# 9_ZynTra-USB2_0.net
KiCad netlist of a schematic drawn in Altium Designer
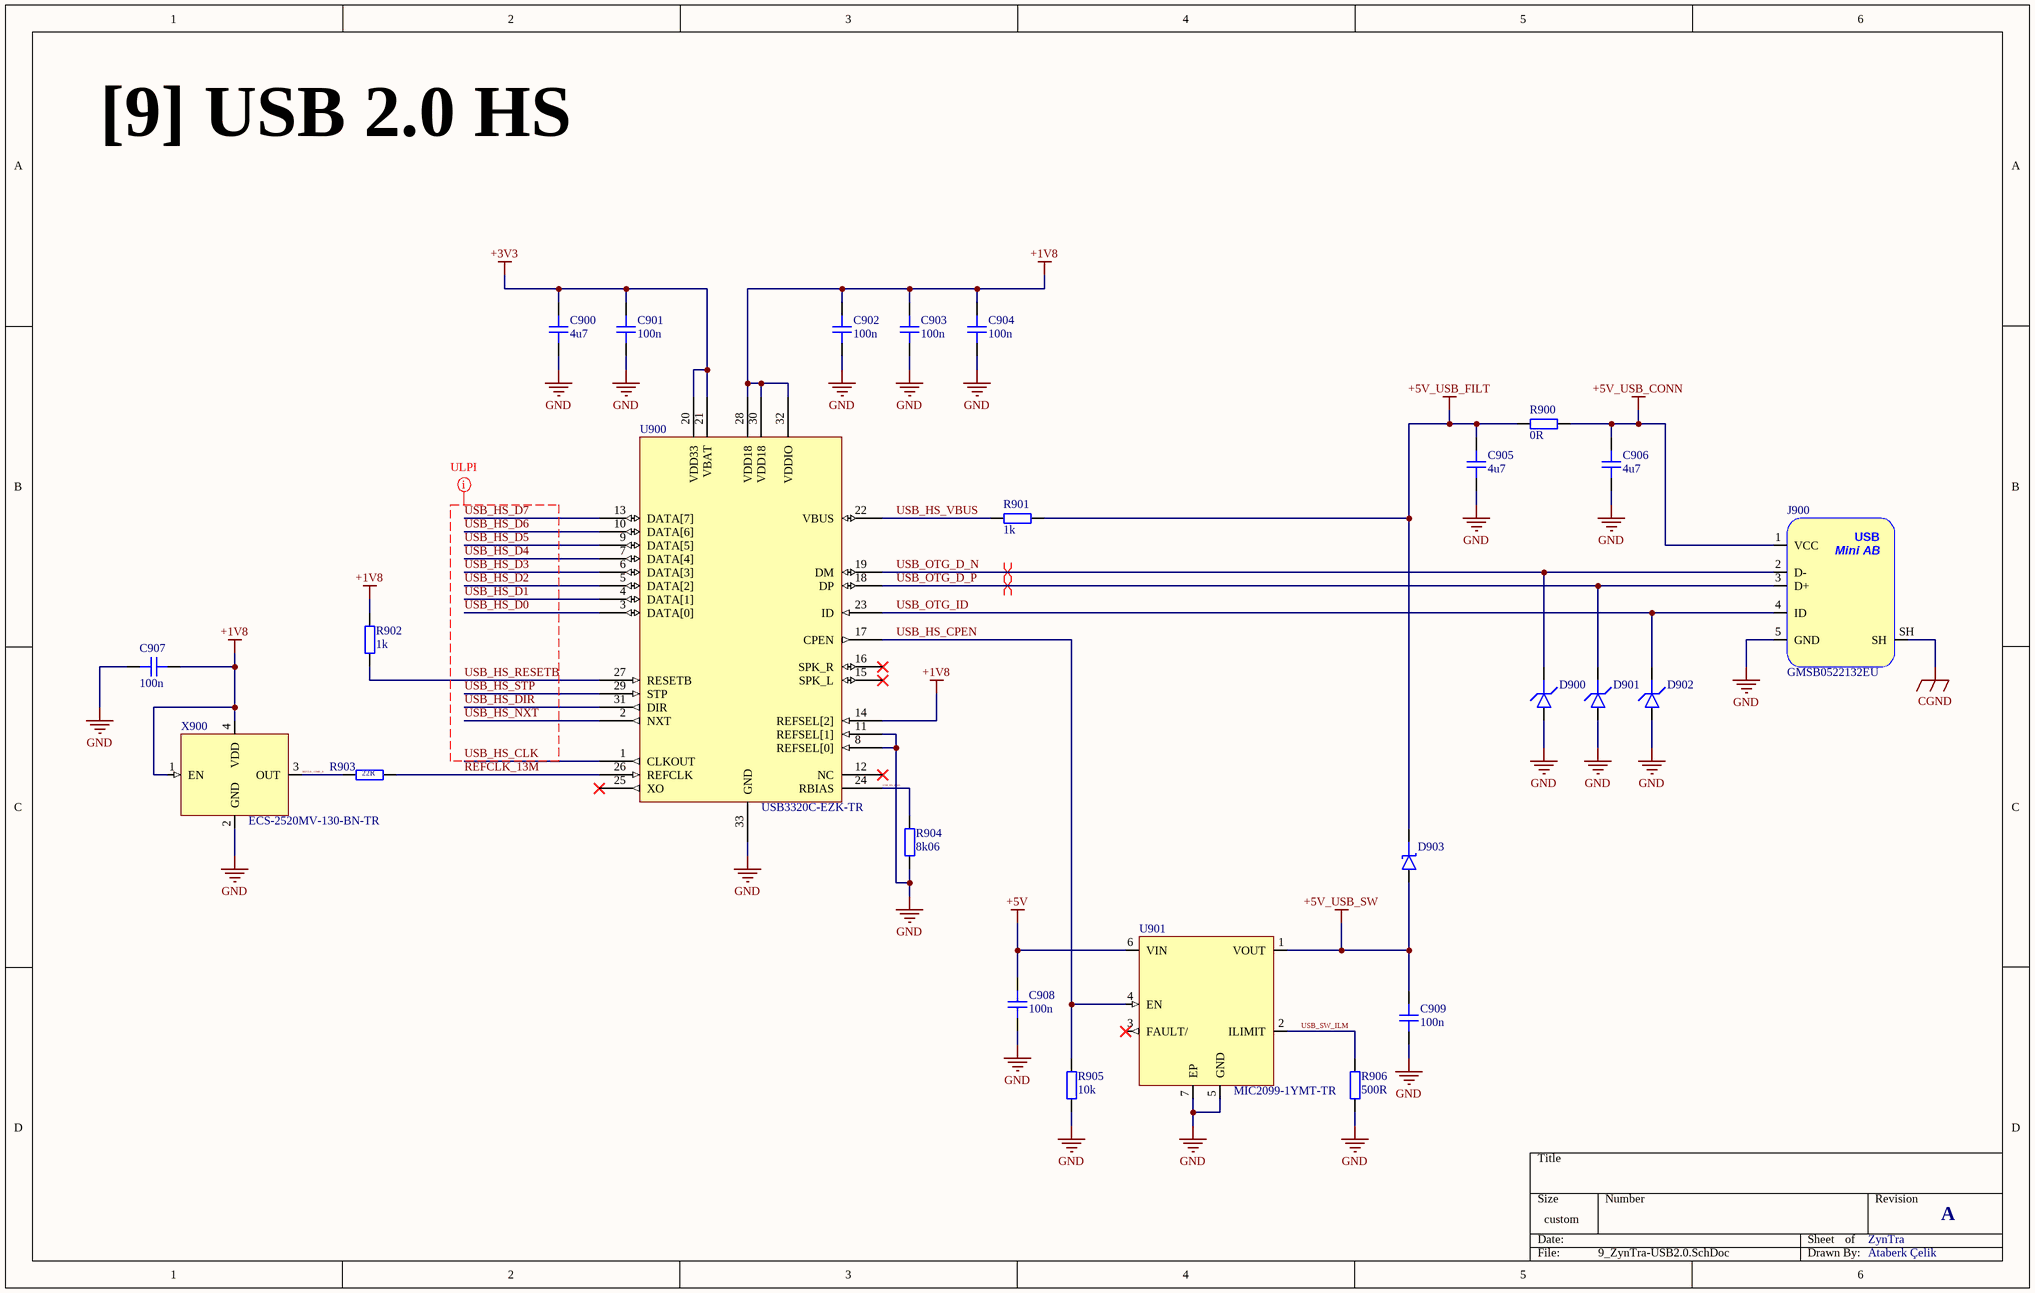
[diagram p0: 9_ZynTra-USB2.0.SchDoc]

(export (version "E")
  (design (tool "Eeschema 10.0.6"))
  (components
    (comp (ref "C900")
      (value "4u7")
      (footprint "CAP_0402")
      (description "Capacitor SMD 0402")
      (libsource (lib "Schematic-Lib-PhilsLab") (part "CAP_0402"))
    )
    (comp (ref "C901")
      (value "100n")
      (footprint "CAP_0201")
      (description "Capacitor SMD 0201")
      (libsource (lib "Schematic-Lib-PhilsLab") (part "CAP_0201"))
    )
    (comp (ref "C902")
      (value "100n")
      (footprint "CAP_0201")
      (description "Capacitor SMD 0201")
      (libsource (lib "Schematic-Lib-PhilsLab") (part "CAP_0201"))
    )
    (comp (ref "C903")
      (value "100n")
      (footprint "CAP_0201")
      (description "Capacitor SMD 0201")
      (libsource (lib "Schematic-Lib-PhilsLab") (part "CAP_0201"))
    )
    (comp (ref "C904")
      (value "100n")
      (footprint "CAP_0201")
      (description "Capacitor SMD 0201")
      (libsource (lib "Schematic-Lib-PhilsLab") (part "CAP_0201"))
    )
    (comp (ref "C905")
      (value "4u7")
      (footprint "CAP_0402")
      (description "Capacitor SMD 0402")
      (libsource (lib "Schematic-Lib-PhilsLab") (part "CAP_0402"))
    )
    (comp (ref "C906")
      (value "4u7")
      (footprint "CAP_0402")
      (description "Capacitor SMD 0402")
      (libsource (lib "Schematic-Lib-PhilsLab") (part "CAP_0402"))
    )
    (comp (ref "C907")
      (value "100n")
      (footprint "CAP_0201")
      (description "Capacitor SMD 0201")
      (libsource (lib "Schematic-Lib-PhilsLab") (part "CAP_0201"))
    )
    (comp (ref "C908")
      (value "100n")
      (footprint "CAP_0201")
      (description "Capacitor SMD 0201")
      (libsource (lib "Schematic-Lib-PhilsLab") (part "CAP_0201"))
    )
    (comp (ref "C909")
      (value "100n")
      (footprint "CAP_0201")
      (description "Capacitor SMD 0201")
      (libsource (lib "Schematic-Lib-PhilsLab") (part "CAP_0201"))
    )
    (comp (ref "D900")
      (value "D_TVS_0402")
      (footprint "D_0402")
      (description "Diode TVS / ESD 0402")
      (libsource (lib "Schematic-Lib-PhilsLab") (part "D_TVS_0402"))
    )
    (comp (ref "D901")
      (value "D_TVS_0402")
      (footprint "D_0402")
      (description "Diode TVS / ESD 0402")
      (libsource (lib "Schematic-Lib-PhilsLab") (part "D_TVS_0402"))
    )
    (comp (ref "D902")
      (value "D_TVS_0402")
      (footprint "D_0402")
      (description "Diode TVS / ESD 0402")
      (libsource (lib "Schematic-Lib-PhilsLab") (part "D_TVS_0402"))
    )
    (comp (ref "D903")
      (value "D_SCHOTTKY_SOD_323")
      (footprint "SOD-323")
      (description "Diode Schottky SMD SOD-323")
      (libsource (lib "Schematic-Lib-PhilsLab") (part "D_SCHOTTKY_SOD_323"))
    )
    (comp (ref "J900")
      (value "GMSB0522132EU")
      (footprint "GMSB0522132EU")
      (description "USB 2.0 Mini AB Receptacle Right Angle Through-Hole")
      (fields (field (name "MANUFACTURER") "Amphenol"))
      (libsource (lib "Schematic-Lib-PhilsLab") (part "GMSB0522132EU"))
    )
    (comp (ref "R900")
      (value "0R")
      (footprint "RES_0402")
      (description "Resistor SMD 0402")
      (libsource (lib "Schematic-Lib-PhilsLab") (part "RES_0402"))
    )
    (comp (ref "R901")
      (value "1k")
      (footprint "RES_0402")
      (description "Resistor SMD 0402")
      (libsource (lib "Schematic-Lib-PhilsLab") (part "RES_0402"))
    )
    (comp (ref "R902")
      (value "1k")
      (footprint "RES_0402")
      (description "Resistor SMD 0402")
      (libsource (lib "Schematic-Lib-PhilsLab") (part "RES_0402"))
    )
    (comp (ref "R903")
      (value "22R")
      (footprint "RES_0402")
      (description "Resistor SMD 0402")
      (libsource (lib "Schematic-Lib-PhilsLab") (part "RES_0402"))
    )
    (comp (ref "R904")
      (value "8k06")
      (footprint "RES_0402")
      (description "Resistor SMD 0402")
      (libsource (lib "Schematic-Lib-PhilsLab") (part "RES_0402"))
    )
    (comp (ref "R905")
      (value "10k")
      (footprint "RES_0402")
      (description "Resistor SMD 0402")
      (libsource (lib "Schematic-Lib-PhilsLab") (part "RES_0402"))
    )
    (comp (ref "R906")
      (value "500R")
      (footprint "RES_0402")
      (description "Resistor SMD 0402")
      (libsource (lib "Schematic-Lib-PhilsLab") (part "RES_0402"))
    )
    (comp (ref "U900")
      (value "USB3320C-EZK-TR")
      (footprint "32-QFN, 5x5mm")
      (description "Highly Integrated Full Featured Hi-Speed USB 2.0 ULPI\r\nTransceiver")
      (fields (field (name "MANUFACTURER") "Microchip"))
      (libsource (lib "AtaSchLib") (part "USB3320C-EZK-TR"))
    )
    (comp (ref "U901")
      (value "MIC2099-1YMT-TR")
      (footprint "6-1.6x1.6mm TMLF")
      (fields (field (name "MANUFACTURER") "Microchip"))
      (libsource (lib "AtaSchLib") (part "MIC2099-1YMT-TR"))
    )
    (comp (ref "X900")
      (value "ECS-2520MV-130-BN-TR")
      (footprint "XTAL_2520")
      (fields (field (name "MANUFACTURER") "ECS"))
      (libsource (lib "Schematic-Lib-PhilsLab") (part "ECS-2520MV-130-BN-TR"))
    )
  )
  (nets
    (net (code "1") (name "+1V8") (class "Default")
      (node (ref "C902") (pin "2") (pinfunction "2_2") (pintype "passive"))
      (node (ref "C903") (pin "2") (pinfunction "2_2") (pintype "passive"))
      (node (ref "C904") (pin "2") (pinfunction "2_2") (pintype "passive"))
      (node (ref "C907") (pin "1") (pinfunction "1_1") (pintype "passive"))
      (node (ref "R902") (pin "2") (pinfunction "2_2") (pintype "passive"))
      (node (ref "U900") (pin "14") (pinfunction "REFSEL[2]_14") (pintype "input"))
      (node (ref "U900") (pin "28") (pinfunction "VDD18_28") (pintype "power_in"))
      (node (ref "U900") (pin "30") (pinfunction "VDD18_30") (pintype "power_in"))
      (node (ref "U900") (pin "32") (pinfunction "VDDIO_32") (pintype "power_in"))
      (node (ref "X900") (pin "1") (pinfunction "EN_1") (pintype "input"))
      (node (ref "X900") (pin "4") (pinfunction "VDD_4") (pintype "power_in"))
    )
    (net (code "2") (name "+3V3") (class "Default")
      (node (ref "C900") (pin "2") (pinfunction "2_2") (pintype "passive"))
      (node (ref "C901") (pin "2") (pinfunction "2_2") (pintype "passive"))
      (node (ref "U900") (pin "20") (pinfunction "VDD33_20") (pintype "power_in"))
      (node (ref "U900") (pin "21") (pinfunction "VBAT_21") (pintype "power_in"))
    )
    (net (code "3") (name "+5V") (class "Default")
      (node (ref "C908") (pin "2") (pinfunction "2_2") (pintype "passive"))
      (node (ref "U901") (pin "6") (pinfunction "VIN_6") (pintype "power_in"))
    )
    (net (code "4") (name "+5V_USB_CONN") (class "Default")
      (node (ref "C906") (pin "2") (pinfunction "2_2") (pintype "passive"))
      (node (ref "J900") (pin "1") (pinfunction "VCC_1") (pintype "power_in"))
      (node (ref "R900") (pin "2") (pinfunction "2_2") (pintype "passive"))
    )
    (net (code "5") (name "+5V_USB_FILT") (class "Default")
      (node (ref "C905") (pin "2") (pinfunction "2_2") (pintype "passive"))
      (node (ref "D903") (pin "K") (pinfunction "K_K") (pintype "passive"))
      (node (ref "R900") (pin "1") (pinfunction "1_1") (pintype "passive"))
      (node (ref "R901") (pin "2") (pinfunction "2_2") (pintype "passive"))
    )
    (net (code "6") (name "+5V_USB_SW") (class "Default")
      (node (ref "C909") (pin "2") (pinfunction "2_2") (pintype "passive"))
      (node (ref "D903") (pin "A") (pinfunction "A_A") (pintype "passive"))
      (node (ref "U901") (pin "1") (pinfunction "VOUT_1") (pintype "power_in"))
    )
    (net (code "7") (name "/REFCLK_13M") (class "Default")
      (node (ref "R903") (pin "2") (pinfunction "2_2") (pintype "passive"))
      (node (ref "U900") (pin "26") (pinfunction "REFCLK_26") (pintype "input"))
    )
    (net (code "8") (name "/REFCLK_13MH_R") (class "Default")
      (node (ref "R903") (pin "1") (pinfunction "1_1") (pintype "passive"))
      (node (ref "X900") (pin "3") (pinfunction "OUT_3") (pintype "passive"))
    )
    (net (code "9") (name "/USB_HS_BIAS") (class "Default")
      (node (ref "R904") (pin "1") (pinfunction "1_1") (pintype "passive"))
      (node (ref "U900") (pin "24") (pinfunction "RBIAS_24") (pintype "power_in"))
    )
    (net (code "10") (name "/USB_HS_CLK") (class "Default")
      (node (ref "U900") (pin "1") (pinfunction "CLKOUT_1") (pintype "output"))
    )
    (net (code "11") (name "/USB_HS_CPEN") (class "Default")
      (node (ref "R905") (pin "1") (pinfunction "1_1") (pintype "passive"))
      (node (ref "U900") (pin "17") (pinfunction "CPEN_17") (pintype "output"))
      (node (ref "U901") (pin "4") (pinfunction "EN_4") (pintype "input"))
    )
    (net (code "12") (name "/USB_HS_D0") (class "Default")
      (node (ref "U900") (pin "3") (pinfunction "DATA[0]_3") (pintype "bidirectional"))
    )
    (net (code "13") (name "/USB_HS_D1") (class "Default")
      (node (ref "U900") (pin "4") (pinfunction "DATA[1]_4") (pintype "bidirectional"))
    )
    (net (code "14") (name "/USB_HS_D2") (class "Default")
      (node (ref "U900") (pin "5") (pinfunction "DATA[2]_5") (pintype "bidirectional"))
    )
    (net (code "15") (name "/USB_HS_D3") (class "Default")
      (node (ref "U900") (pin "6") (pinfunction "DATA[3]_6") (pintype "bidirectional"))
    )
    (net (code "16") (name "/USB_HS_D4") (class "Default")
      (node (ref "U900") (pin "7") (pinfunction "DATA[4]_7") (pintype "bidirectional"))
    )
    (net (code "17") (name "/USB_HS_D5") (class "Default")
      (node (ref "U900") (pin "9") (pinfunction "DATA[5]_9") (pintype "bidirectional"))
    )
    (net (code "18") (name "/USB_HS_D6") (class "Default")
      (node (ref "U900") (pin "10") (pinfunction "DATA[6]_10") (pintype "bidirectional"))
    )
    (net (code "19") (name "/USB_HS_D7") (class "Default")
      (node (ref "U900") (pin "13") (pinfunction "DATA[7]_13") (pintype "bidirectional"))
    )
    (net (code "20") (name "/USB_HS_DIR") (class "Default")
      (node (ref "U900") (pin "31") (pinfunction "DIR_31") (pintype "output"))
    )
    (net (code "21") (name "/USB_HS_NXT") (class "Default")
      (node (ref "U900") (pin "2") (pinfunction "NXT_2") (pintype "output"))
    )
    (net (code "22") (name "/USB_HS_RESETB") (class "Default")
      (node (ref "R902") (pin "1") (pinfunction "1_1") (pintype "passive"))
      (node (ref "U900") (pin "27") (pinfunction "RESETB_27") (pintype "input"))
    )
    (net (code "23") (name "/USB_HS_STP") (class "Default")
      (node (ref "U900") (pin "29") (pinfunction "STP_29") (pintype "input"))
    )
    (net (code "24") (name "/USB_HS_VBUS") (class "Default")
      (node (ref "R901") (pin "1") (pinfunction "1_1") (pintype "passive"))
      (node (ref "U900") (pin "22") (pinfunction "VBUS_22") (pintype "bidirectional"))
    )
    (net (code "25") (name "/USB_OTG_D_N") (class "Default")
      (node (ref "D900") (pin "K") (pinfunction "K_K") (pintype "passive"))
      (node (ref "J900") (pin "2") (pinfunction "D-_2") (pintype "bidirectional"))
      (node (ref "U900") (pin "19") (pinfunction "DM_19") (pintype "bidirectional"))
    )
    (net (code "26") (name "/USB_OTG_D_P") (class "Default")
      (node (ref "D901") (pin "K") (pinfunction "K_K") (pintype "passive"))
      (node (ref "J900") (pin "3") (pinfunction "D+_3") (pintype "bidirectional"))
      (node (ref "U900") (pin "18") (pinfunction "DP_18") (pintype "bidirectional"))
    )
    (net (code "27") (name "/USB_OTG_ID") (class "Default")
      (node (ref "D902") (pin "K") (pinfunction "K_K") (pintype "passive"))
      (node (ref "J900") (pin "4") (pinfunction "ID_4") (pintype "passive"))
      (node (ref "U900") (pin "23") (pinfunction "ID_23") (pintype "input"))
    )
    (net (code "28") (name "/USB_SW_ILM") (class "Default")
      (node (ref "R906") (pin "1") (pinfunction "1_1") (pintype "passive"))
      (node (ref "U901") (pin "2") (pinfunction "ILIMIT_2") (pintype "power_in"))
    )
    (net (code "29") (name "CGND") (class "Default")
      (node (ref "J900") (pin "SH") (pinfunction "SH_SH") (pintype "power_in"))
    )
    (net (code "30") (name "GND") (class "Default")
      (node (ref "C900") (pin "1") (pinfunction "1_1") (pintype "passive"))
      (node (ref "C901") (pin "1") (pinfunction "1_1") (pintype "passive"))
      (node (ref "C902") (pin "1") (pinfunction "1_1") (pintype "passive"))
      (node (ref "C903") (pin "1") (pinfunction "1_1") (pintype "passive"))
      (node (ref "C904") (pin "1") (pinfunction "1_1") (pintype "passive"))
      (node (ref "C905") (pin "1") (pinfunction "1_1") (pintype "passive"))
      (node (ref "C906") (pin "1") (pinfunction "1_1") (pintype "passive"))
      (node (ref "C907") (pin "2") (pinfunction "2_2") (pintype "passive"))
      (node (ref "C908") (pin "1") (pinfunction "1_1") (pintype "passive"))
      (node (ref "C909") (pin "1") (pinfunction "1_1") (pintype "passive"))
      (node (ref "D900") (pin "A") (pinfunction "A_A") (pintype "passive"))
      (node (ref "D901") (pin "A") (pinfunction "A_A") (pintype "passive"))
      (node (ref "D902") (pin "A") (pinfunction "A_A") (pintype "passive"))
      (node (ref "J900") (pin "5") (pinfunction "GND_5") (pintype "power_in"))
      (node (ref "R904") (pin "2") (pinfunction "2_2") (pintype "passive"))
      (node (ref "R905") (pin "2") (pinfunction "2_2") (pintype "passive"))
      (node (ref "R906") (pin "2") (pinfunction "2_2") (pintype "passive"))
      (node (ref "U900") (pin "11") (pinfunction "REFSEL[1]_11") (pintype "input"))
      (node (ref "U900") (pin "33") (pinfunction "GND_33") (pintype "power_in"))
      (node (ref "U900") (pin "8") (pinfunction "REFSEL[0]_8") (pintype "input"))
      (node (ref "U901") (pin "5") (pinfunction "GND_5") (pintype "power_in"))
      (node (ref "U901") (pin "7") (pinfunction "EP_7") (pintype "power_in"))
      (node (ref "X900") (pin "2") (pinfunction "GND_2") (pintype "power_in"))
    )
    (net (code "31") (name "unconnected-(U900-NC-Pad12)") (class "Default")
      (node (ref "U900") (pin "12") (pinfunction "NC_12") (pintype "passive+no_connect"))
    )
    (net (code "32") (name "unconnected-(U900-SPK_L-Pad15)") (class "Default")
      (node (ref "U900") (pin "15") (pinfunction "SPK_L_15") (pintype "bidirectional+no_connect"))
    )
    (net (code "33") (name "unconnected-(U900-SPK_R-Pad16)") (class "Default")
      (node (ref "U900") (pin "16") (pinfunction "SPK_R_16") (pintype "bidirectional+no_connect"))
    )
    (net (code "34") (name "unconnected-(U900-XO-Pad25)") (class "Default")
      (node (ref "U900") (pin "25") (pinfunction "XO_25") (pintype "output+no_connect"))
    )
    (net (code "35") (name "unconnected-(U901-FAULT{slash}-Pad3)") (class "Default")
      (node (ref "U901") (pin "3") (pinfunction "FAULT/_3") (pintype "output+no_connect"))
    )
  )
)
